# TSOC_RS485_EM.net
KiCad netlist of a schematic drawn in EAGLE
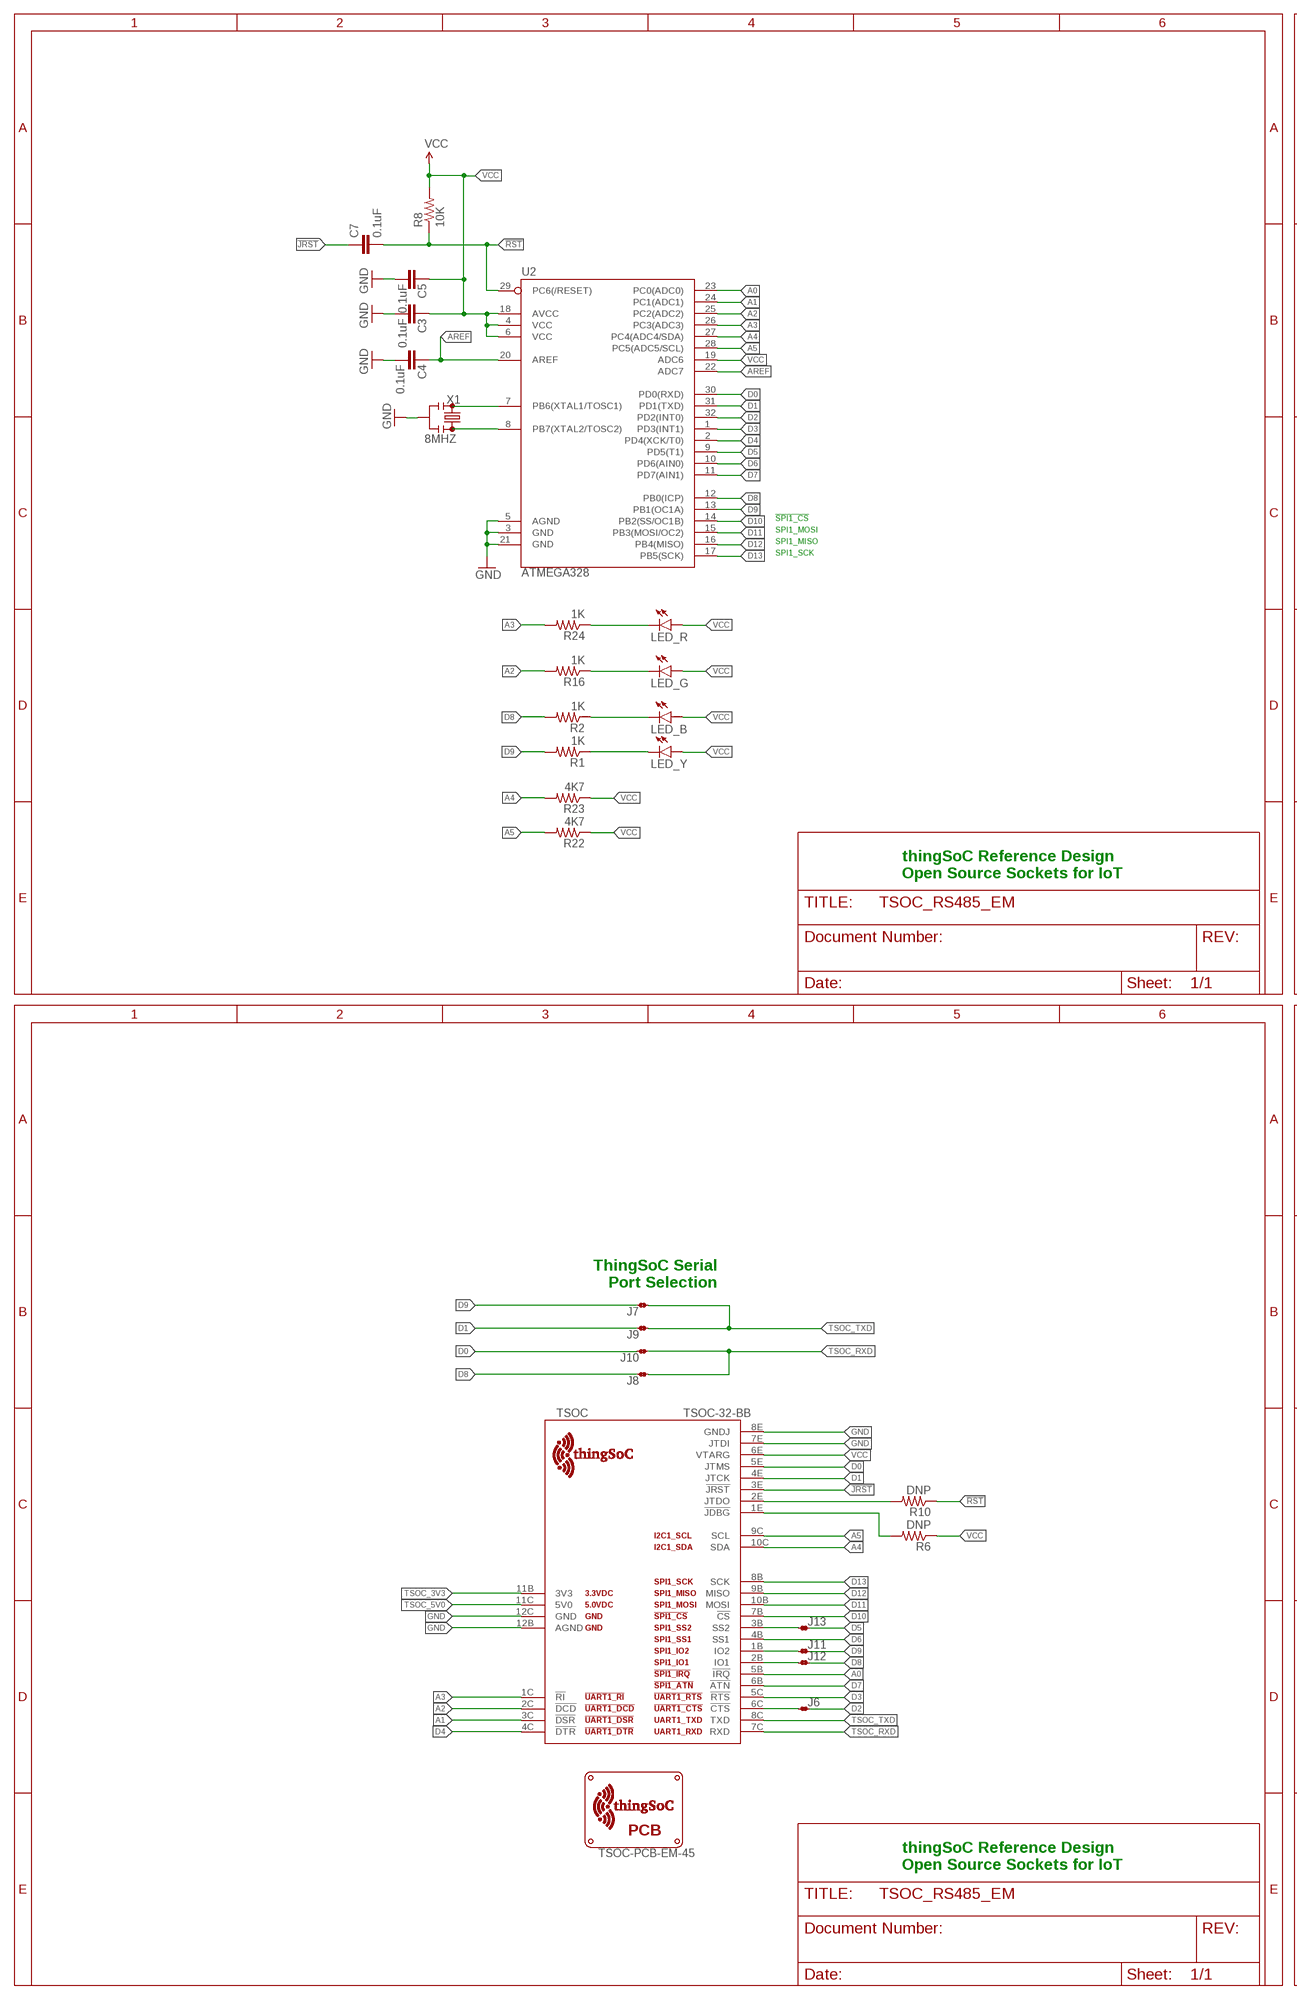
[diagram p0: schematic, sheet 1, part 1 of 2]
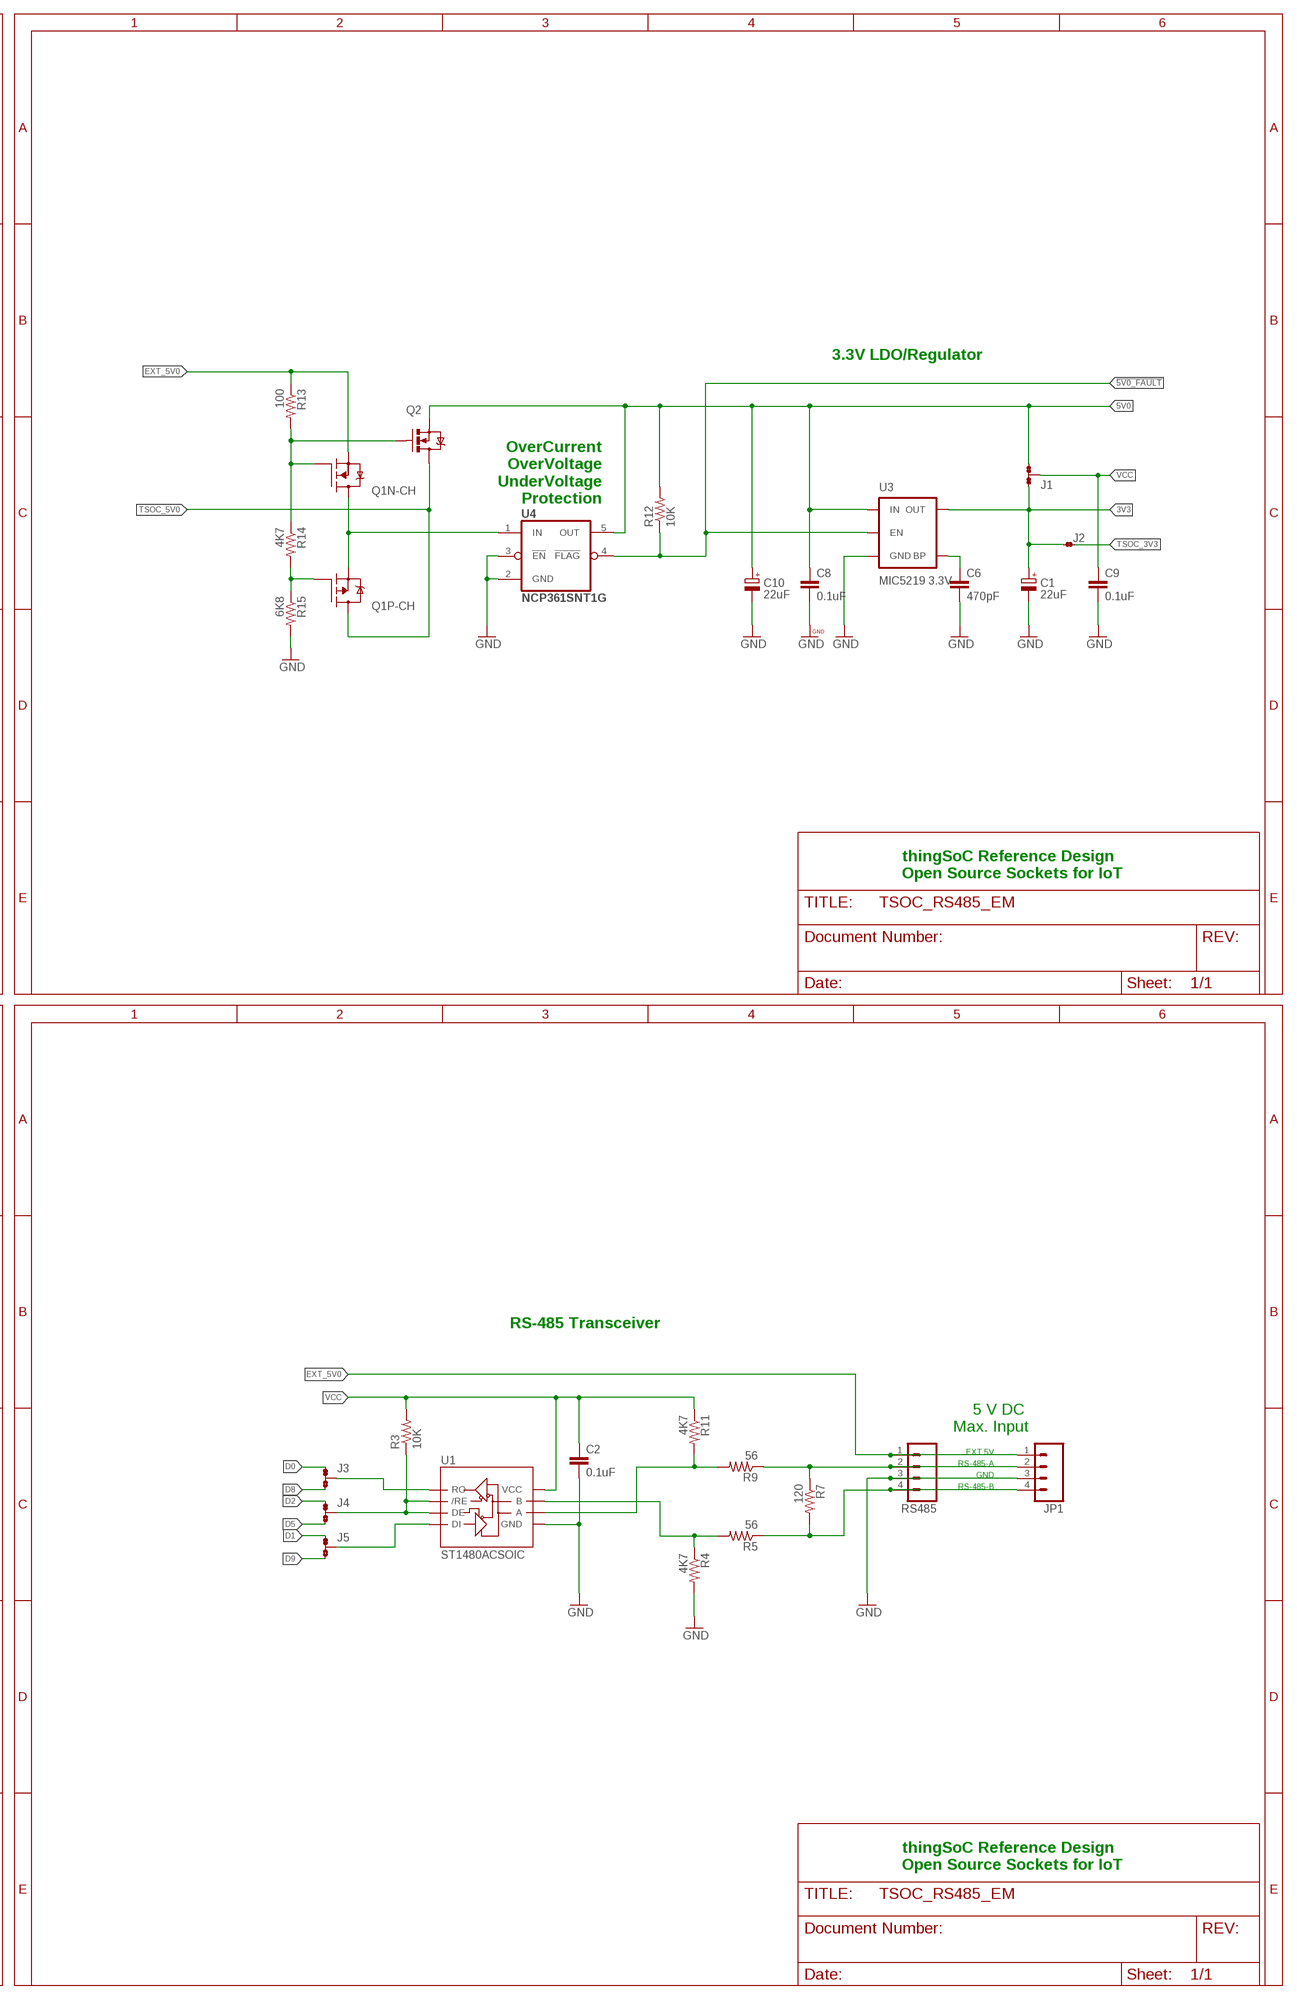
[diagram p1: schematic, sheet 1, part 2 of 2]

(export (version "E")
  (design (tool "Eeschema 10.0.6"))
  (components
    (comp (ref "C1")
      (value "22uF")
      (footprint "eagle-import:SMC_B")
      (libsource (lib "eagle-import") (part "CPOL-EUSMCB"))
    )
    (comp (ref "C2")
      (value "0.1uF")
      (footprint "eagle-import:0402-CAP")
      (libsource (lib "eagle-import") (part "CAP0402-CAP"))
    )
    (comp (ref "C3")
      (value "0.1uF")
      (footprint "eagle-import:0402-CAP")
      (libsource (lib "eagle-import") (part "CAP0402-CAP"))
    )
    (comp (ref "C4")
      (value "0.1uF")
      (footprint "eagle-import:0402-CAP")
      (libsource (lib "eagle-import") (part "CAP0402-CAP"))
    )
    (comp (ref "C5")
      (value "0.1uF")
      (footprint "eagle-import:0402-CAP")
      (libsource (lib "eagle-import") (part "CAP0402-CAP"))
    )
    (comp (ref "C6")
      (value "470pF")
      (footprint "eagle-import:0402-CAP")
      (libsource (lib "eagle-import") (part "CAP0402-CAP"))
    )
    (comp (ref "C7")
      (value "0.1uF")
      (footprint "eagle-import:0402-CAP")
      (libsource (lib "eagle-import") (part "CAP0402-CAP"))
    )
    (comp (ref "C8")
      (value "0.1uF")
      (footprint "eagle-import:0402-CAP")
      (libsource (lib "eagle-import") (part "CAP0402-CAP"))
    )
    (comp (ref "C9")
      (value "0.1uF")
      (footprint "eagle-import:0402-CAP")
      (libsource (lib "eagle-import") (part "CAP0402-CAP"))
    )
    (comp (ref "C10")
      (value "22uF")
      (footprint "eagle-import:SMC_B")
      (libsource (lib "eagle-import") (part "CPOL-EUSMCB"))
    )
    (comp (ref "J1")
      (value "JMP-3-1_2")
      (footprint "eagle-import:JMP-3-1_2")
      (libsource (lib "eagle-import") (part "JMP-3-1_2"))
    )
    (comp (ref "J2")
      (value "JMP-2-NC")
      (footprint "eagle-import:JMP-2-NC")
      (libsource (lib "eagle-import") (part "JMP-2-NC"))
    )
    (comp (ref "J3")
      (value "JMP-3-1_2")
      (footprint "eagle-import:JMP-3-1_2")
      (libsource (lib "eagle-import") (part "TSOC_RS485_EM_JMP-3-1_2"))
    )
    (comp (ref "J4")
      (value "JMP-3-1_2")
      (footprint "eagle-import:JMP-3-1_2")
      (libsource (lib "eagle-import") (part "TSOC_RS485_EM_JMP-3-1_2"))
    )
    (comp (ref "J5")
      (value "JMP-3-1_2")
      (footprint "eagle-import:JMP-3-1_2")
      (libsource (lib "eagle-import") (part "TSOC_RS485_EM_JMP-3-1_2"))
    )
    (comp (ref "J6")
      (value "JMP-2-NO")
      (footprint "eagle-import:JMP-2-NO")
      (libsource (lib "eagle-import") (part "JMP-2-NO"))
    )
    (comp (ref "J7")
      (value "JMP-2-NO")
      (footprint "eagle-import:JMP-2-NO")
      (libsource (lib "eagle-import") (part "JMP-2-NO"))
    )
    (comp (ref "J8")
      (value "JMP-2-NO")
      (footprint "eagle-import:JMP-2-NO")
      (libsource (lib "eagle-import") (part "JMP-2-NO"))
    )
    (comp (ref "J9")
      (value "JMP-2-NO")
      (footprint "eagle-import:JMP-2-NO")
      (libsource (lib "eagle-import") (part "JMP-2-NO"))
    )
    (comp (ref "J10")
      (value "JMP-2-NO")
      (footprint "eagle-import:JMP-2-NO")
      (libsource (lib "eagle-import") (part "JMP-2-NO"))
    )
    (comp (ref "J11")
      (value "JMP-2-NC")
      (footprint "eagle-import:JMP-2-NC")
      (libsource (lib "eagle-import") (part "JMP-2-NC"))
    )
    (comp (ref "J12")
      (value "JMP-2-NC")
      (footprint "eagle-import:JMP-2-NC")
      (libsource (lib "eagle-import") (part "JMP-2-NC"))
    )
    (comp (ref "J13")
      (value "JMP-2-NC")
      (footprint "eagle-import:JMP-2-NC")
      (libsource (lib "eagle-import") (part "JMP-2-NC"))
    )
    (comp (ref "JP1")
      (value "M04PTH")
      (footprint "eagle-import:1X04")
      (libsource (lib "eagle-import") (part "M04PTH"))
    )
    (comp (ref "LED_B")
      (value "LED0603")
      (footprint "eagle-import:LED-0603")
      (libsource (lib "eagle-import") (part "LED0603"))
    )
    (comp (ref "LED_G")
      (value "LED0603")
      (footprint "eagle-import:LED-0603")
      (libsource (lib "eagle-import") (part "LED0603"))
    )
    (comp (ref "LED_R")
      (value "LED0603")
      (footprint "eagle-import:LED-0603")
      (libsource (lib "eagle-import") (part "LED0603"))
    )
    (comp (ref "LED_Y")
      (value "LED0603")
      (footprint "eagle-import:LED-0603")
      (libsource (lib "eagle-import") (part "LED0603"))
    )
    (comp (ref "Q1")
      (value "FDC6420C")
      (footprint "eagle-import:SOT95P280X110-6N")
      (libsource (lib "eagle-import") (part "FDC6420C"))
    )
    (comp (ref "Q2")
      (value "MOSFET-NCHANNELAO3404A")
      (footprint "eagle-import:SOT23-3")
      (libsource (lib "eagle-import") (part "MOSFET-NCHANNELAO3404A"))
    )
    (comp (ref "R1")
      (value "1K")
      (footprint "eagle-import:0402-RES")
      (libsource (lib "eagle-import") (part "RESISTOR0402"))
    )
    (comp (ref "R2")
      (value "1K")
      (footprint "eagle-import:0402-RES")
      (libsource (lib "eagle-import") (part "RESISTOR0402"))
    )
    (comp (ref "R3")
      (value "10K")
      (footprint "eagle-import:0402-RES")
      (libsource (lib "eagle-import") (part "RESISTOR0402"))
    )
    (comp (ref "R4")
      (value "4K7")
      (footprint "eagle-import:0402-RES")
      (libsource (lib "eagle-import") (part "RESISTOR0402"))
    )
    (comp (ref "R5")
      (value "56")
      (footprint "eagle-import:0402-RES")
      (libsource (lib "eagle-import") (part "RESISTOR0402"))
    )
    (comp (ref "R6")
      (value "DNP")
      (footprint "eagle-import:0402-RES")
      (libsource (lib "eagle-import") (part "RESISTOR0402"))
    )
    (comp (ref "R7")
      (value "120")
      (footprint "eagle-import:0402-RES")
      (libsource (lib "eagle-import") (part "RESISTOR0402"))
    )
    (comp (ref "R8")
      (value "10K")
      (footprint "eagle-import:0402-RES")
      (libsource (lib "eagle-import") (part "RESISTOR0402"))
    )
    (comp (ref "R9")
      (value "56")
      (footprint "eagle-import:0402-RES")
      (libsource (lib "eagle-import") (part "RESISTOR0402"))
    )
    (comp (ref "R10")
      (value "DNP")
      (footprint "eagle-import:0402-RES")
      (libsource (lib "eagle-import") (part "RESISTOR0402"))
    )
    (comp (ref "R11")
      (value "4K7")
      (footprint "eagle-import:0402-RES")
      (libsource (lib "eagle-import") (part "RESISTOR0402"))
    )
    (comp (ref "R12")
      (value "10K")
      (footprint "eagle-import:0402-RES")
      (libsource (lib "eagle-import") (part "RESISTOR0402"))
    )
    (comp (ref "R13")
      (value "100")
      (footprint "eagle-import:0402-RES")
      (libsource (lib "eagle-import") (part "RESISTOR0402"))
    )
    (comp (ref "R14")
      (value "4K7")
      (footprint "eagle-import:0402-RES")
      (libsource (lib "eagle-import") (part "RESISTOR0402"))
    )
    (comp (ref "R15")
      (value "6K8")
      (footprint "eagle-import:0402-RES")
      (libsource (lib "eagle-import") (part "RESISTOR0402"))
    )
    (comp (ref "R16")
      (value "1K")
      (footprint "eagle-import:0402-RES")
      (libsource (lib "eagle-import") (part "RESISTOR0402"))
    )
    (comp (ref "R22")
      (value "4K7")
      (footprint "eagle-import:0402-RES")
      (libsource (lib "eagle-import") (part "RESISTOR0402"))
    )
    (comp (ref "R23")
      (value "4K7")
      (footprint "eagle-import:0402-RES")
      (libsource (lib "eagle-import") (part "RESISTOR0402"))
    )
    (comp (ref "R24")
      (value "1K")
      (footprint "eagle-import:0402-RES")
      (libsource (lib "eagle-import") (part "RESISTOR0402"))
    )
    (comp (ref "RS485")
      (value "M04SCREW")
      (footprint "eagle-import:SCREWTERMINAL-3.5MM-4")
      (libsource (lib "eagle-import") (part "M04SCREW"))
    )
    (comp (ref "TSOC")
      (value "TSOC-32-BB")
      (footprint "eagle-import:TSOC-BB-S32")
      (libsource (lib "eagle-import") (part "TSOC-32-BB"))
    )
    (comp (ref "U$1")
      (value "TSOC-PCB-EM-45")
      (footprint "eagle-import:TSOC-EM-BB-45MM")
      (libsource (lib "eagle-import") (part "TSOC-PCB-EM-45"))
    )
    (comp (ref "U1")
      (value "ST1480ACSOIC")
      (footprint "eagle-import:SO08")
      (libsource (lib "eagle-import") (part "ST1480ACSOIC"))
    )
    (comp (ref "U2")
      (value "ATMEGA328")
      (footprint "eagle-import:TQFP32-08")
      (libsource (lib "eagle-import") (part "ATMEGA168"))
    )
    (comp (ref "U3")
      (value "MIC5219 3.3V")
      (footprint "eagle-import:SOT23-5")
      (libsource (lib "eagle-import") (part "V_REG_MIC52193.3V"))
    )
    (comp (ref "U4")
      (value "NCP361SNT1G")
      (footprint "eagle-import:SOP95P275X110-5N")
      (libsource (lib "eagle-import") (part "NCP361SNT1G"))
    )
    (comp (ref "X1")
      (value "8MHZ")
      (footprint "eagle-import:RESONATOR-SMD")
      (libsource (lib "eagle-import") (part "RESONATOR8MHZ"))
    )
  )
  (nets
    (net (code "1") (name "/~{5V0_FAULT}") (class "Default")
      (node (ref "R12") (pin "1") (pinfunction "1_1") (pintype "passive"))
      (node (ref "U3") (pin "3") (pinfunction "EN_3") (pintype "input"))
      (node (ref "U4") (pin "4") (pinfunction "~{FLAG}_4") (pintype "input"))
    )
    (net (code "2") (name "/~{JRST}") (class "Default")
      (node (ref "C7") (pin "1") (pinfunction "1_1") (pintype "passive"))
      (node (ref "TSOC") (pin "3E") (pinfunction "~{JRST}_3E") (pintype "bidirectional"))
    )
    (net (code "3") (name "/~{RST}") (class "Default")
      (node (ref "C7") (pin "2") (pinfunction "2_2") (pintype "passive"))
      (node (ref "R10") (pin "1") (pinfunction "1_1") (pintype "passive"))
      (node (ref "R8") (pin "1") (pinfunction "1_1") (pintype "passive"))
      (node (ref "U2") (pin "29") (pinfunction "PC6(/RESET)_29") (pintype "bidirectional"))
    )
    (net (code "4") (name "3V3") (class "Default")
      (node (ref "C1") (pin "+") (pinfunction "+_+") (pintype "passive"))
      (node (ref "J1") (pin "1") (pinfunction "1_1") (pintype "passive"))
      (node (ref "J2") (pin "1") (pinfunction "1_1") (pintype "passive"))
      (node (ref "U3") (pin "5") (pinfunction "OUT_5") (pintype "passive"))
    )
    (net (code "5") (name "5V0") (class "Default")
      (node (ref "C10") (pin "+") (pinfunction "+_+") (pintype "passive"))
      (node (ref "C8") (pin "1") (pinfunction "1_1") (pintype "passive"))
      (node (ref "J1") (pin "3") (pinfunction "3_3") (pintype "passive"))
      (node (ref "Q2") (pin "2") (pinfunction "S_2") (pintype "passive"))
      (node (ref "R12") (pin "2") (pinfunction "2_2") (pintype "passive"))
      (node (ref "U3") (pin "1") (pinfunction "IN_1") (pintype "input"))
      (node (ref "U4") (pin "5") (pinfunction "OUT_5") (pintype "output"))
    )
    (net (code "6") (name "A0") (class "Default")
      (node (ref "TSOC") (pin "5B") (pinfunction "~{IRQ}_5B") (pintype "bidirectional"))
      (node (ref "U2") (pin "23") (pinfunction "PC0(ADC0)_23") (pintype "bidirectional"))
    )
    (net (code "7") (name "A1") (class "Default")
      (node (ref "TSOC") (pin "3C") (pinfunction "~{DSR}_3C") (pintype "bidirectional"))
      (node (ref "U2") (pin "24") (pinfunction "PC1(ADC1)_24") (pintype "bidirectional"))
    )
    (net (code "8") (name "A2") (class "Default")
      (node (ref "R16") (pin "2") (pinfunction "2_2") (pintype "passive"))
      (node (ref "TSOC") (pin "2C") (pinfunction "~{DCD}_2C") (pintype "bidirectional"))
      (node (ref "U2") (pin "25") (pinfunction "PC2(ADC2)_25") (pintype "bidirectional"))
    )
    (net (code "9") (name "A3") (class "Default")
      (node (ref "R24") (pin "2") (pinfunction "2_2") (pintype "passive"))
      (node (ref "TSOC") (pin "1C") (pinfunction "~{RI}_1C") (pintype "bidirectional"))
      (node (ref "U2") (pin "26") (pinfunction "PC3(ADC3)_26") (pintype "bidirectional"))
    )
    (net (code "10") (name "A4") (class "Default")
      (node (ref "R23") (pin "2") (pinfunction "2_2") (pintype "passive"))
      (node (ref "TSOC") (pin "10C") (pinfunction "SDA_10C") (pintype "bidirectional"))
      (node (ref "U2") (pin "27") (pinfunction "PC4(ADC4/SDA)_27") (pintype "bidirectional"))
    )
    (net (code "11") (name "A5") (class "Default")
      (node (ref "R22") (pin "2") (pinfunction "2_2") (pintype "passive"))
      (node (ref "TSOC") (pin "9C") (pinfunction "SCL_9C") (pintype "bidirectional"))
      (node (ref "U2") (pin "28") (pinfunction "PC5(ADC5/SCL)_28") (pintype "bidirectional"))
    )
    (net (code "12") (name "AREF") (class "Default")
      (node (ref "C4") (pin "2") (pinfunction "2_2") (pintype "passive"))
      (node (ref "U2") (pin "20") (pinfunction "AREF_20") (pintype "bidirectional"))
      (node (ref "U2") (pin "22") (pinfunction "ADC7_22") (pintype "bidirectional"))
    )
    (net (code "13") (name "D0") (class "Default")
      (node (ref "J10") (pin "2") (pinfunction "2_2") (pintype "passive"))
      (node (ref "J3") (pin "1") (pinfunction "1_1") (pintype "passive"))
      (node (ref "TSOC") (pin "5E") (pinfunction "JTMS_5E") (pintype "bidirectional"))
      (node (ref "U2") (pin "30") (pinfunction "PD0(RXD)_30") (pintype "bidirectional"))
    )
    (net (code "14") (name "D1") (class "Default")
      (node (ref "J5") (pin "1") (pinfunction "1_1") (pintype "passive"))
      (node (ref "J9") (pin "2") (pinfunction "2_2") (pintype "passive"))
      (node (ref "TSOC") (pin "4E") (pinfunction "JTCK_4E") (pintype "bidirectional"))
      (node (ref "U2") (pin "31") (pinfunction "PD1(TXD)_31") (pintype "bidirectional"))
    )
    (net (code "15") (name "D2") (class "Default")
      (node (ref "J4") (pin "1") (pinfunction "1_1") (pintype "passive"))
      (node (ref "J6") (pin "2") (pinfunction "2_2") (pintype "passive"))
      (node (ref "U2") (pin "32") (pinfunction "PD2(INT0)_32") (pintype "bidirectional"))
    )
    (net (code "16") (name "D3") (class "Default")
      (node (ref "TSOC") (pin "5C") (pinfunction "~{RTS}_5C") (pintype "bidirectional"))
      (node (ref "U2") (pin "1") (pinfunction "PD3(INT1)_1") (pintype "bidirectional"))
    )
    (net (code "17") (name "D4") (class "Default")
      (node (ref "TSOC") (pin "4C") (pinfunction "~{DTR}_4C") (pintype "bidirectional"))
      (node (ref "U2") (pin "2") (pinfunction "PD4(XCK/T0)_2") (pintype "bidirectional"))
    )
    (net (code "18") (name "D5") (class "Default")
      (node (ref "J13") (pin "2") (pinfunction "2_2") (pintype "passive"))
      (node (ref "J4") (pin "3") (pinfunction "3_3") (pintype "passive"))
      (node (ref "U2") (pin "9") (pinfunction "PD5(T1)_9") (pintype "bidirectional"))
    )
    (net (code "19") (name "D6") (class "Default")
      (node (ref "TSOC") (pin "4B") (pinfunction "SS1_4B") (pintype "bidirectional"))
      (node (ref "U2") (pin "10") (pinfunction "PD6(AIN0)_10") (pintype "bidirectional"))
    )
    (net (code "20") (name "D7") (class "Default")
      (node (ref "TSOC") (pin "6B") (pinfunction "~{ATN}_6B") (pintype "bidirectional"))
      (node (ref "U2") (pin "11") (pinfunction "PD7(AIN1)_11") (pintype "bidirectional"))
    )
    (net (code "21") (name "D8") (class "Default")
      (node (ref "J12") (pin "2") (pinfunction "2_2") (pintype "passive"))
      (node (ref "J3") (pin "3") (pinfunction "3_3") (pintype "passive"))
      (node (ref "J8") (pin "2") (pinfunction "2_2") (pintype "passive"))
      (node (ref "R2") (pin "2") (pinfunction "2_2") (pintype "passive"))
      (node (ref "U2") (pin "12") (pinfunction "PB0(ICP)_12") (pintype "bidirectional"))
    )
    (net (code "22") (name "D9") (class "Default")
      (node (ref "J11") (pin "2") (pinfunction "2_2") (pintype "passive"))
      (node (ref "J5") (pin "3") (pinfunction "3_3") (pintype "passive"))
      (node (ref "J7") (pin "2") (pinfunction "2_2") (pintype "passive"))
      (node (ref "R1") (pin "2") (pinfunction "2_2") (pintype "passive"))
      (node (ref "U2") (pin "13") (pinfunction "PB1(OC1A)_13") (pintype "bidirectional"))
    )
    (net (code "23") (name "D10") (class "Default")
      (node (ref "TSOC") (pin "7B") (pinfunction "~{CS}_7B") (pintype "bidirectional"))
      (node (ref "U2") (pin "14") (pinfunction "PB2(SS/OC1B)_14") (pintype "bidirectional"))
    )
    (net (code "24") (name "D11") (class "Default")
      (node (ref "TSOC") (pin "10B") (pinfunction "MOSI_10B") (pintype "bidirectional"))
      (node (ref "U2") (pin "15") (pinfunction "PB3(MOSI/OC2)_15") (pintype "bidirectional"))
    )
    (net (code "25") (name "D12") (class "Default")
      (node (ref "TSOC") (pin "9B") (pinfunction "MISO_9B") (pintype "bidirectional"))
      (node (ref "U2") (pin "16") (pinfunction "PB4(MISO)_16") (pintype "bidirectional"))
    )
    (net (code "26") (name "D13") (class "Default")
      (node (ref "TSOC") (pin "8B") (pinfunction "SCK_8B") (pintype "bidirectional"))
      (node (ref "U2") (pin "17") (pinfunction "PB5(SCK)_17") (pintype "bidirectional"))
    )
    (net (code "27") (name "EXT_5V0") (class "Default")
      (node (ref "JP1") (pin "1") (pinfunction "1_1") (pintype "passive"))
      (node (ref "Q1") (pin "5") (pinfunction "S_5") (pintype "passive"))
      (node (ref "R13") (pin "1") (pinfunction "1_1") (pintype "passive"))
      (node (ref "RS485") (pin "1") (pinfunction "1_1") (pintype "passive"))
    )
    (net (code "28") (name "GND") (class "Default")
      (node (ref "C1") (pin "-") (pinfunction "-_-") (pintype "passive"))
      (node (ref "C10") (pin "-") (pinfunction "-_-") (pintype "passive"))
      (node (ref "C2") (pin "2") (pinfunction "2_2") (pintype "passive"))
      (node (ref "C3") (pin "1") (pinfunction "1_1") (pintype "passive"))
      (node (ref "C4") (pin "1") (pinfunction "1_1") (pintype "passive"))
      (node (ref "C5") (pin "1") (pinfunction "1_1") (pintype "passive"))
      (node (ref "C6") (pin "2") (pinfunction "2_2") (pintype "passive"))
      (node (ref "C8") (pin "2") (pinfunction "2_2") (pintype "passive"))
      (node (ref "C9") (pin "2") (pinfunction "2_2") (pintype "passive"))
      (node (ref "JP1") (pin "3") (pinfunction "3_3") (pintype "passive"))
      (node (ref "R15") (pin "2") (pinfunction "2_2") (pintype "passive"))
      (node (ref "R4") (pin "2") (pinfunction "2_2") (pintype "passive"))
      (node (ref "RS485") (pin "3") (pinfunction "3_3") (pintype "passive"))
      (node (ref "TSOC") (pin "12B") (pinfunction "AGND_12B") (pintype "bidirectional"))
      (node (ref "TSOC") (pin "12C") (pinfunction "GND_12C") (pintype "bidirectional"))
      (node (ref "TSOC") (pin "7E") (pinfunction "JTDI_7E") (pintype "bidirectional"))
      (node (ref "TSOC") (pin "8E") (pinfunction "GNDJ_8E") (pintype "bidirectional"))
      (node (ref "U1") (pin "5") (pinfunction "GND_5") (pintype "bidirectional"))
      (node (ref "U2") (pin "21") (pinfunction "GND_21") (pintype "bidirectional"))
      (node (ref "U2") (pin "3") (pinfunction "GND_3") (pintype "bidirectional"))
      (node (ref "U2") (pin "5") (pinfunction "AGND_5") (pintype "bidirectional"))
      (node (ref "U3") (pin "2") (pinfunction "GND_2") (pintype "input"))
      (node (ref "U4") (pin "2") (pinfunction "GND_2") (pintype "passive"))
      (node (ref "U4") (pin "3") (pinfunction "~{EN}_3") (pintype "input"))
      (node (ref "X1") (pin "2") (pinfunction "2_2") (pintype "passive"))
    )
    (net (code "29") (name "Net-(JP1-Pad2)") (class "Default")
      (node (ref "JP1") (pin "2") (pinfunction "2_2") (pintype "passive"))
      (node (ref "R7") (pin "1") (pinfunction "1_1") (pintype "passive"))
      (node (ref "R9") (pin "1") (pinfunction "1_1") (pintype "passive"))
      (node (ref "RS485") (pin "2") (pinfunction "2_2") (pintype "passive"))
    )
    (net (code "30") (name "Net-(JP1-Pad4)") (class "Default")
      (node (ref "JP1") (pin "4") (pinfunction "4_4") (pintype "passive"))
      (node (ref "R5") (pin "1") (pinfunction "1_1") (pintype "passive"))
      (node (ref "R7") (pin "2") (pinfunction "2_2") (pintype "passive"))
      (node (ref "RS485") (pin "4") (pinfunction "4_4") (pintype "passive"))
    )
    (net (code "31") (name "Net-(LED_B-PadC)") (class "Default")
      (node (ref "LED_B") (pin "C") (pinfunction "C_C") (pintype "passive"))
      (node (ref "R2") (pin "1") (pinfunction "1_1") (pintype "passive"))
    )
    (net (code "32") (name "Net-(LED_G-PadC)") (class "Default")
      (node (ref "LED_G") (pin "C") (pinfunction "C_C") (pintype "passive"))
      (node (ref "R16") (pin "1") (pinfunction "1_1") (pintype "passive"))
    )
    (net (code "33") (name "Net-(LED_R-PadC)") (class "Default")
      (node (ref "LED_R") (pin "C") (pinfunction "C_C") (pintype "passive"))
      (node (ref "R24") (pin "1") (pinfunction "1_1") (pintype "passive"))
    )
    (net (code "34") (name "Net-(LED_Y-PadC)") (class "Default")
      (node (ref "LED_Y") (pin "C") (pinfunction "C_C") (pintype "passive"))
      (node (ref "R1") (pin "1") (pinfunction "1_1") (pintype "passive"))
    )
    (net (code "35") (name "Net-(Q1A-D)") (class "Default")
      (node (ref "Q1") (pin "2") (pinfunction "S_2") (pintype "passive"))
      (node (ref "Q1") (pin "6") (pinfunction "D_6") (pintype "passive"))
      (node (ref "U4") (pin "1") (pinfunction "IN_1") (pintype "power_in"))
    )
    (net (code "36") (name "Net-(Q1A-G)") (class "Default")
      (node (ref "Q1") (pin "1") (pinfunction "G_1") (pintype "passive"))
      (node (ref "Q2") (pin "1") (pinfunction "G_1") (pintype "passive"))
      (node (ref "R13") (pin "2") (pinfunction "2_2") (pintype "passive"))
      (node (ref "R14") (pin "1") (pinfunction "1_1") (pintype "passive"))
    )
    (net (code "37") (name "Net-(Q1B-G)") (class "Default")
      (node (ref "Q1") (pin "3") (pinfunction "G_3") (pintype "passive"))
      (node (ref "R14") (pin "2") (pinfunction "2_2") (pintype "passive"))
      (node (ref "R15") (pin "1") (pinfunction "1_1") (pintype "passive"))
    )
    (net (code "38") (name "Net-(TSOC-IO1)") (class "Default")
      (node (ref "J12") (pin "1") (pinfunction "1_1") (pintype "passive"))
      (node (ref "TSOC") (pin "2B") (pinfunction "IO1_2B") (pintype "bidirectional"))
    )
    (net (code "39") (name "Net-(TSOC-IO2)") (class "Default")
      (node (ref "J11") (pin "1") (pinfunction "1_1") (pintype "passive"))
      (node (ref "TSOC") (pin "1B") (pinfunction "IO2_1B") (pintype "bidirectional"))
    )
    (net (code "40") (name "Net-(TSOC-JTDO)") (class "Default")
      (node (ref "R10") (pin "2") (pinfunction "2_2") (pintype "passive"))
      (node (ref "TSOC") (pin "2E") (pinfunction "JTDO_2E") (pintype "bidirectional"))
    )
    (net (code "41") (name "Net-(TSOC-SS2)") (class "Default")
      (node (ref "J13") (pin "1") (pinfunction "1_1") (pintype "passive"))
      (node (ref "TSOC") (pin "3B") (pinfunction "SS2_3B") (pintype "bidirectional"))
    )
    (net (code "42") (name "Net-(TSOC-~{CTS})") (class "Default")
      (node (ref "J6") (pin "1") (pinfunction "1_1") (pintype "passive"))
      (node (ref "TSOC") (pin "6C") (pinfunction "~{CTS}_6C") (pintype "bidirectional"))
    )
    (net (code "43") (name "Net-(TSOC-~{JDBG})") (class "Default")
      (node (ref "R6") (pin "2") (pinfunction "2_2") (pintype "passive"))
      (node (ref "TSOC") (pin "1E") (pinfunction "~{JDBG}_1E") (pintype "bidirectional"))
    )
    (net (code "44") (name "Net-(U1-A)") (class "Default")
      (node (ref "R11") (pin "2") (pinfunction "2_2") (pintype "passive"))
      (node (ref "R9") (pin "2") (pinfunction "2_2") (pintype "passive"))
      (node (ref "U1") (pin "6") (pinfunction "A_6") (pintype "bidirectional"))
    )
    (net (code "45") (name "Net-(U1-B)") (class "Default")
      (node (ref "R4") (pin "1") (pinfunction "1_1") (pintype "passive"))
      (node (ref "R5") (pin "2") (pinfunction "2_2") (pintype "passive"))
      (node (ref "U1") (pin "7") (pinfunction "B_7") (pintype "bidirectional"))
    )
    (net (code "46") (name "Net-(U1-DE)") (class "Default")
      (node (ref "J4") (pin "2") (pinfunction "2_2") (pintype "passive"))
      (node (ref "R3") (pin "1") (pinfunction "1_1") (pintype "passive"))
      (node (ref "U1") (pin "2") (pinfunction "/RE_2") (pintype "bidirectional"))
      (node (ref "U1") (pin "3") (pinfunction "DE_3") (pintype "bidirectional"))
    )
    (net (code "47") (name "Net-(U1-DI)") (class "Default")
      (node (ref "J5") (pin "2") (pinfunction "2_2") (pintype "passive"))
      (node (ref "U1") (pin "4") (pinfunction "DI_4") (pintype "bidirectional"))
    )
    (net (code "48") (name "Net-(U1-RO)") (class "Default")
      (node (ref "J3") (pin "2") (pinfunction "2_2") (pintype "passive"))
      (node (ref "U1") (pin "1") (pinfunction "RO_1") (pintype "bidirectional"))
    )
    (net (code "49") (name "Net-(U2-PB6(XTAL1{slash}TOSC1))") (class "Default")
      (node (ref "U2") (pin "7") (pinfunction "PB6(XTAL1/TOSC1)_7") (pintype "bidirectional"))
      (node (ref "X1") (pin "3") (pinfunction "3_3") (pintype "passive"))
    )
    (net (code "50") (name "Net-(U2-PB7(XTAL2{slash}TOSC2))") (class "Default")
      (node (ref "U2") (pin "8") (pinfunction "PB7(XTAL2/TOSC2)_8") (pintype "bidirectional"))
      (node (ref "X1") (pin "1") (pinfunction "1_1") (pintype "passive"))
    )
    (net (code "51") (name "Net-(U3-BP)") (class "Default")
      (node (ref "C6") (pin "1") (pinfunction "1_1") (pintype "passive"))
      (node (ref "U3") (pin "4") (pinfunction "BP_4") (pintype "input"))
    )
    (net (code "52") (name "TSOC_3V3") (class "Default")
      (node (ref "J2") (pin "2") (pinfunction "2_2") (pintype "passive"))
      (node (ref "TSOC") (pin "11B") (pinfunction "3V3_11B") (pintype "bidirectional"))
    )
    (net (code "53") (name "TSOC_5V0") (class "Default")
      (node (ref "Q1") (pin "4") (pinfunction "D_4") (pintype "passive"))
      (node (ref "Q2") (pin "3") (pinfunction "D_3") (pintype "passive"))
      (node (ref "TSOC") (pin "11C") (pinfunction "5V0_11C") (pintype "bidirectional"))
    )
    (net (code "54") (name "TSOC_RXD") (class "Default")
      (node (ref "J10") (pin "1") (pinfunction "1_1") (pintype "passive"))
      (node (ref "J8") (pin "1") (pinfunction "1_1") (pintype "passive"))
      (node (ref "TSOC") (pin "7C") (pinfunction "RXD_7C") (pintype "bidirectional"))
    )
    (net (code "55") (name "TSOC_TXD") (class "Default")
      (node (ref "J7") (pin "1") (pinfunction "1_1") (pintype "passive"))
      (node (ref "J9") (pin "1") (pinfunction "1_1") (pintype "passive"))
      (node (ref "TSOC") (pin "8C") (pinfunction "TXD_8C") (pintype "bidirectional"))
    )
    (net (code "56") (name "VCC") (class "Default")
      (node (ref "C2") (pin "1") (pinfunction "1_1") (pintype "passive"))
      (node (ref "C3") (pin "2") (pinfunction "2_2") (pintype "passive"))
      (node (ref "C5") (pin "2") (pinfunction "2_2") (pintype "passive"))
      (node (ref "C9") (pin "1") (pinfunction "1_1") (pintype "passive"))
      (node (ref "J1") (pin "2") (pinfunction "2_2") (pintype "passive"))
      (node (ref "LED_B") (pin "A") (pinfunction "A_A") (pintype "passive"))
      (node (ref "LED_G") (pin "A") (pinfunction "A_A") (pintype "passive"))
      (node (ref "LED_R") (pin "A") (pinfunction "A_A") (pintype "passive"))
      (node (ref "LED_Y") (pin "A") (pinfunction "A_A") (pintype "passive"))
      (node (ref "R11") (pin "1") (pinfunction "1_1") (pintype "passive"))
      (node (ref "R22") (pin "1") (pinfunction "1_1") (pintype "passive"))
      (node (ref "R23") (pin "1") (pinfunction "1_1") (pintype "passive"))
      (node (ref "R3") (pin "2") (pinfunction "2_2") (pintype "passive"))
      (node (ref "R6") (pin "1") (pinfunction "1_1") (pintype "passive"))
      (node (ref "R8") (pin "2") (pinfunction "2_2") (pintype "passive"))
      (node (ref "TSOC") (pin "6E") (pinfunction "VTARG_6E") (pintype "bidirectional"))
      (node (ref "U1") (pin "8") (pinfunction "VCC_8") (pintype "bidirectional"))
      (node (ref "U2") (pin "18") (pinfunction "AVCC_18") (pintype "bidirectional"))
      (node (ref "U2") (pin "19") (pinfunction "ADC6_19") (pintype "bidirectional"))
      (node (ref "U2") (pin "4") (pinfunction "VCC_4") (pintype "bidirectional"))
      (node (ref "U2") (pin "6") (pinfunction "VCC_6") (pintype "bidirectional"))
    )
  )
)
